# H05-dl.net
KiCad netlist of a schematic drawn in EAGLE
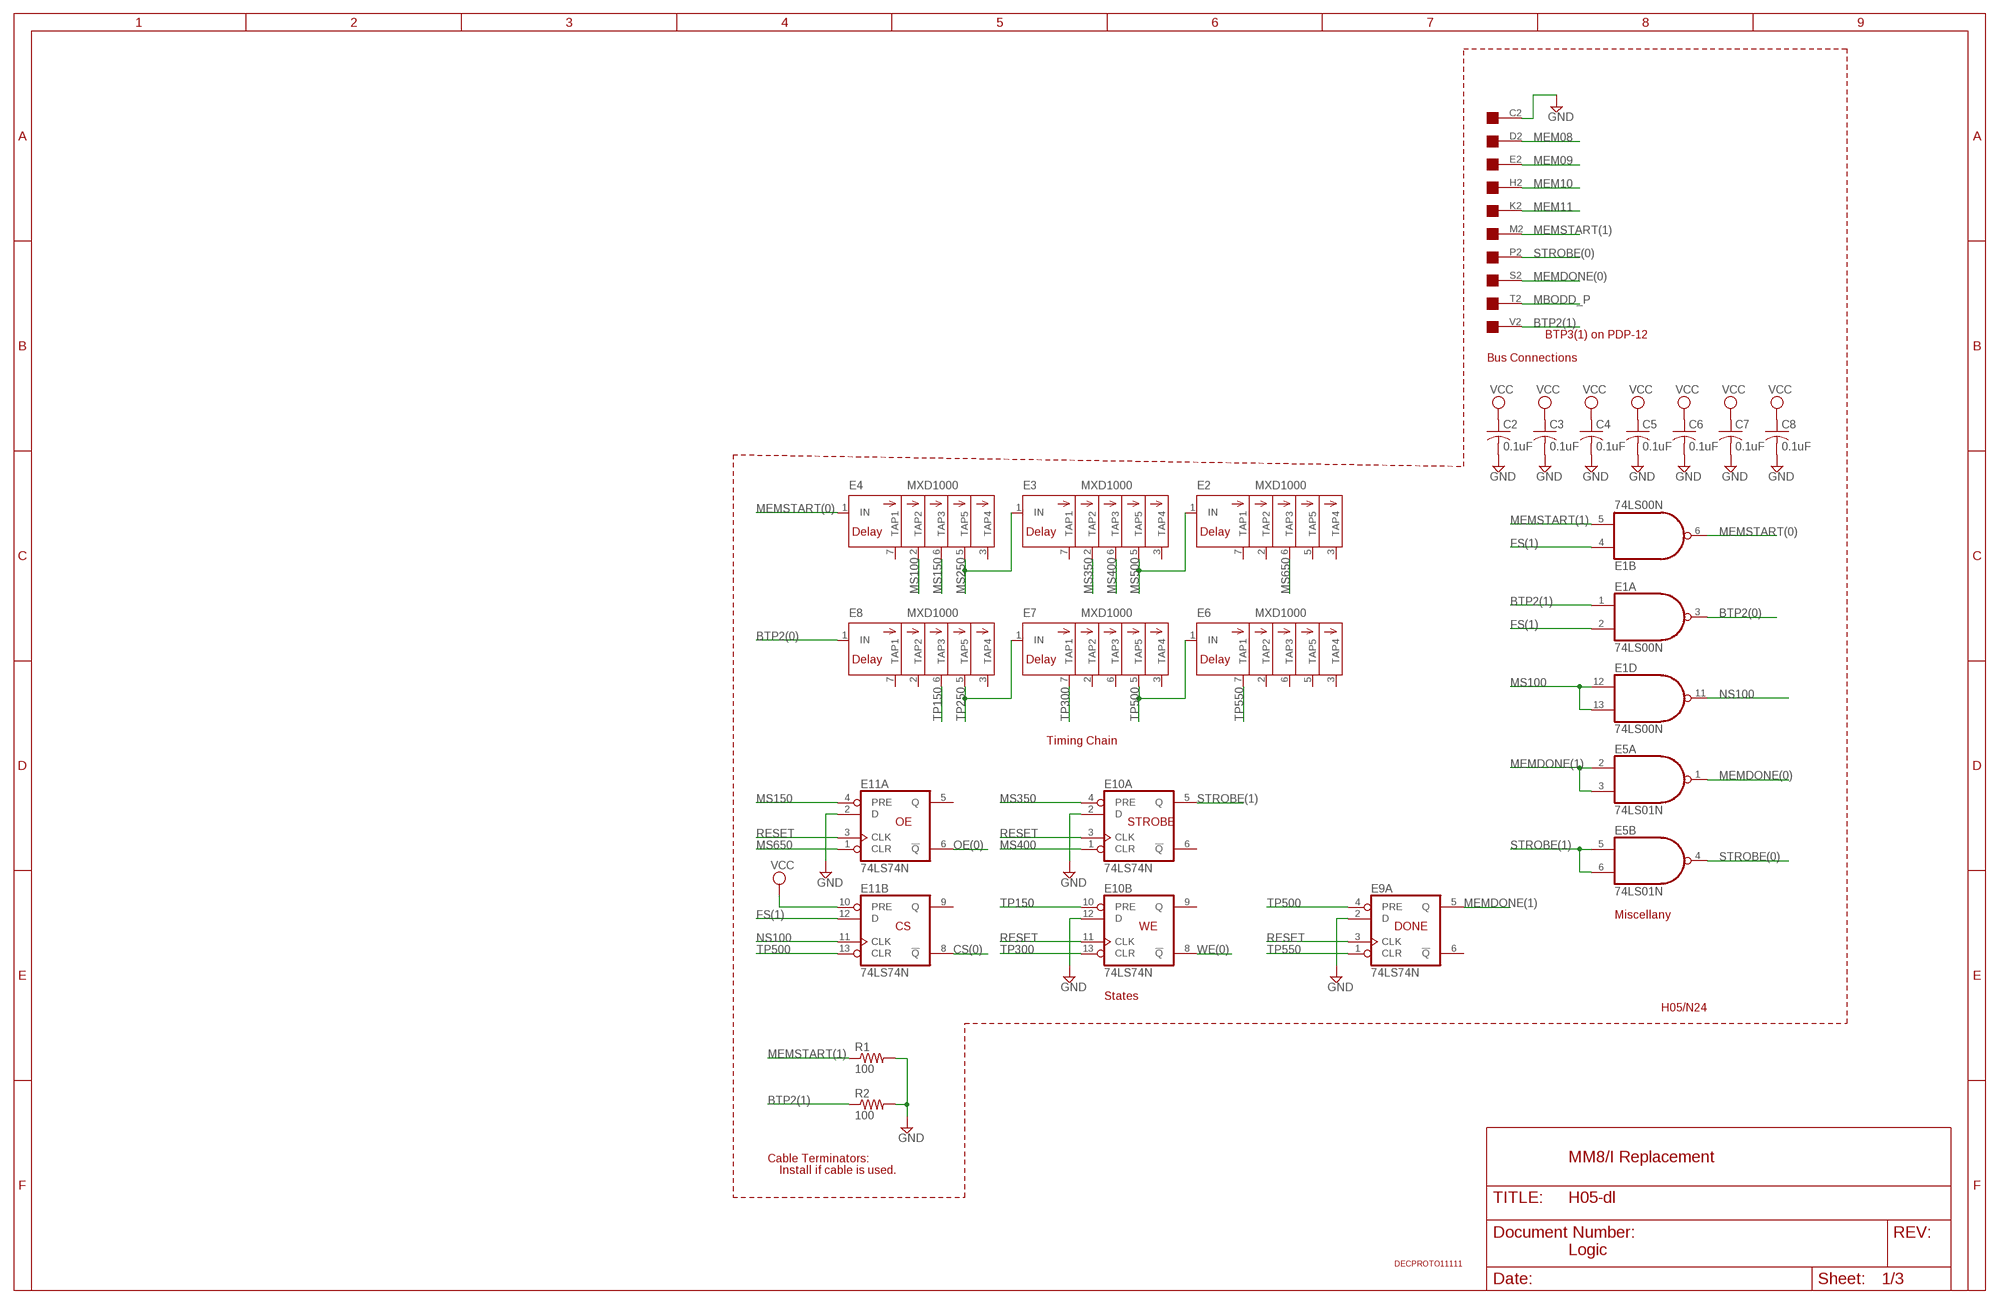
[diagram p0: schematic, sheet 1]
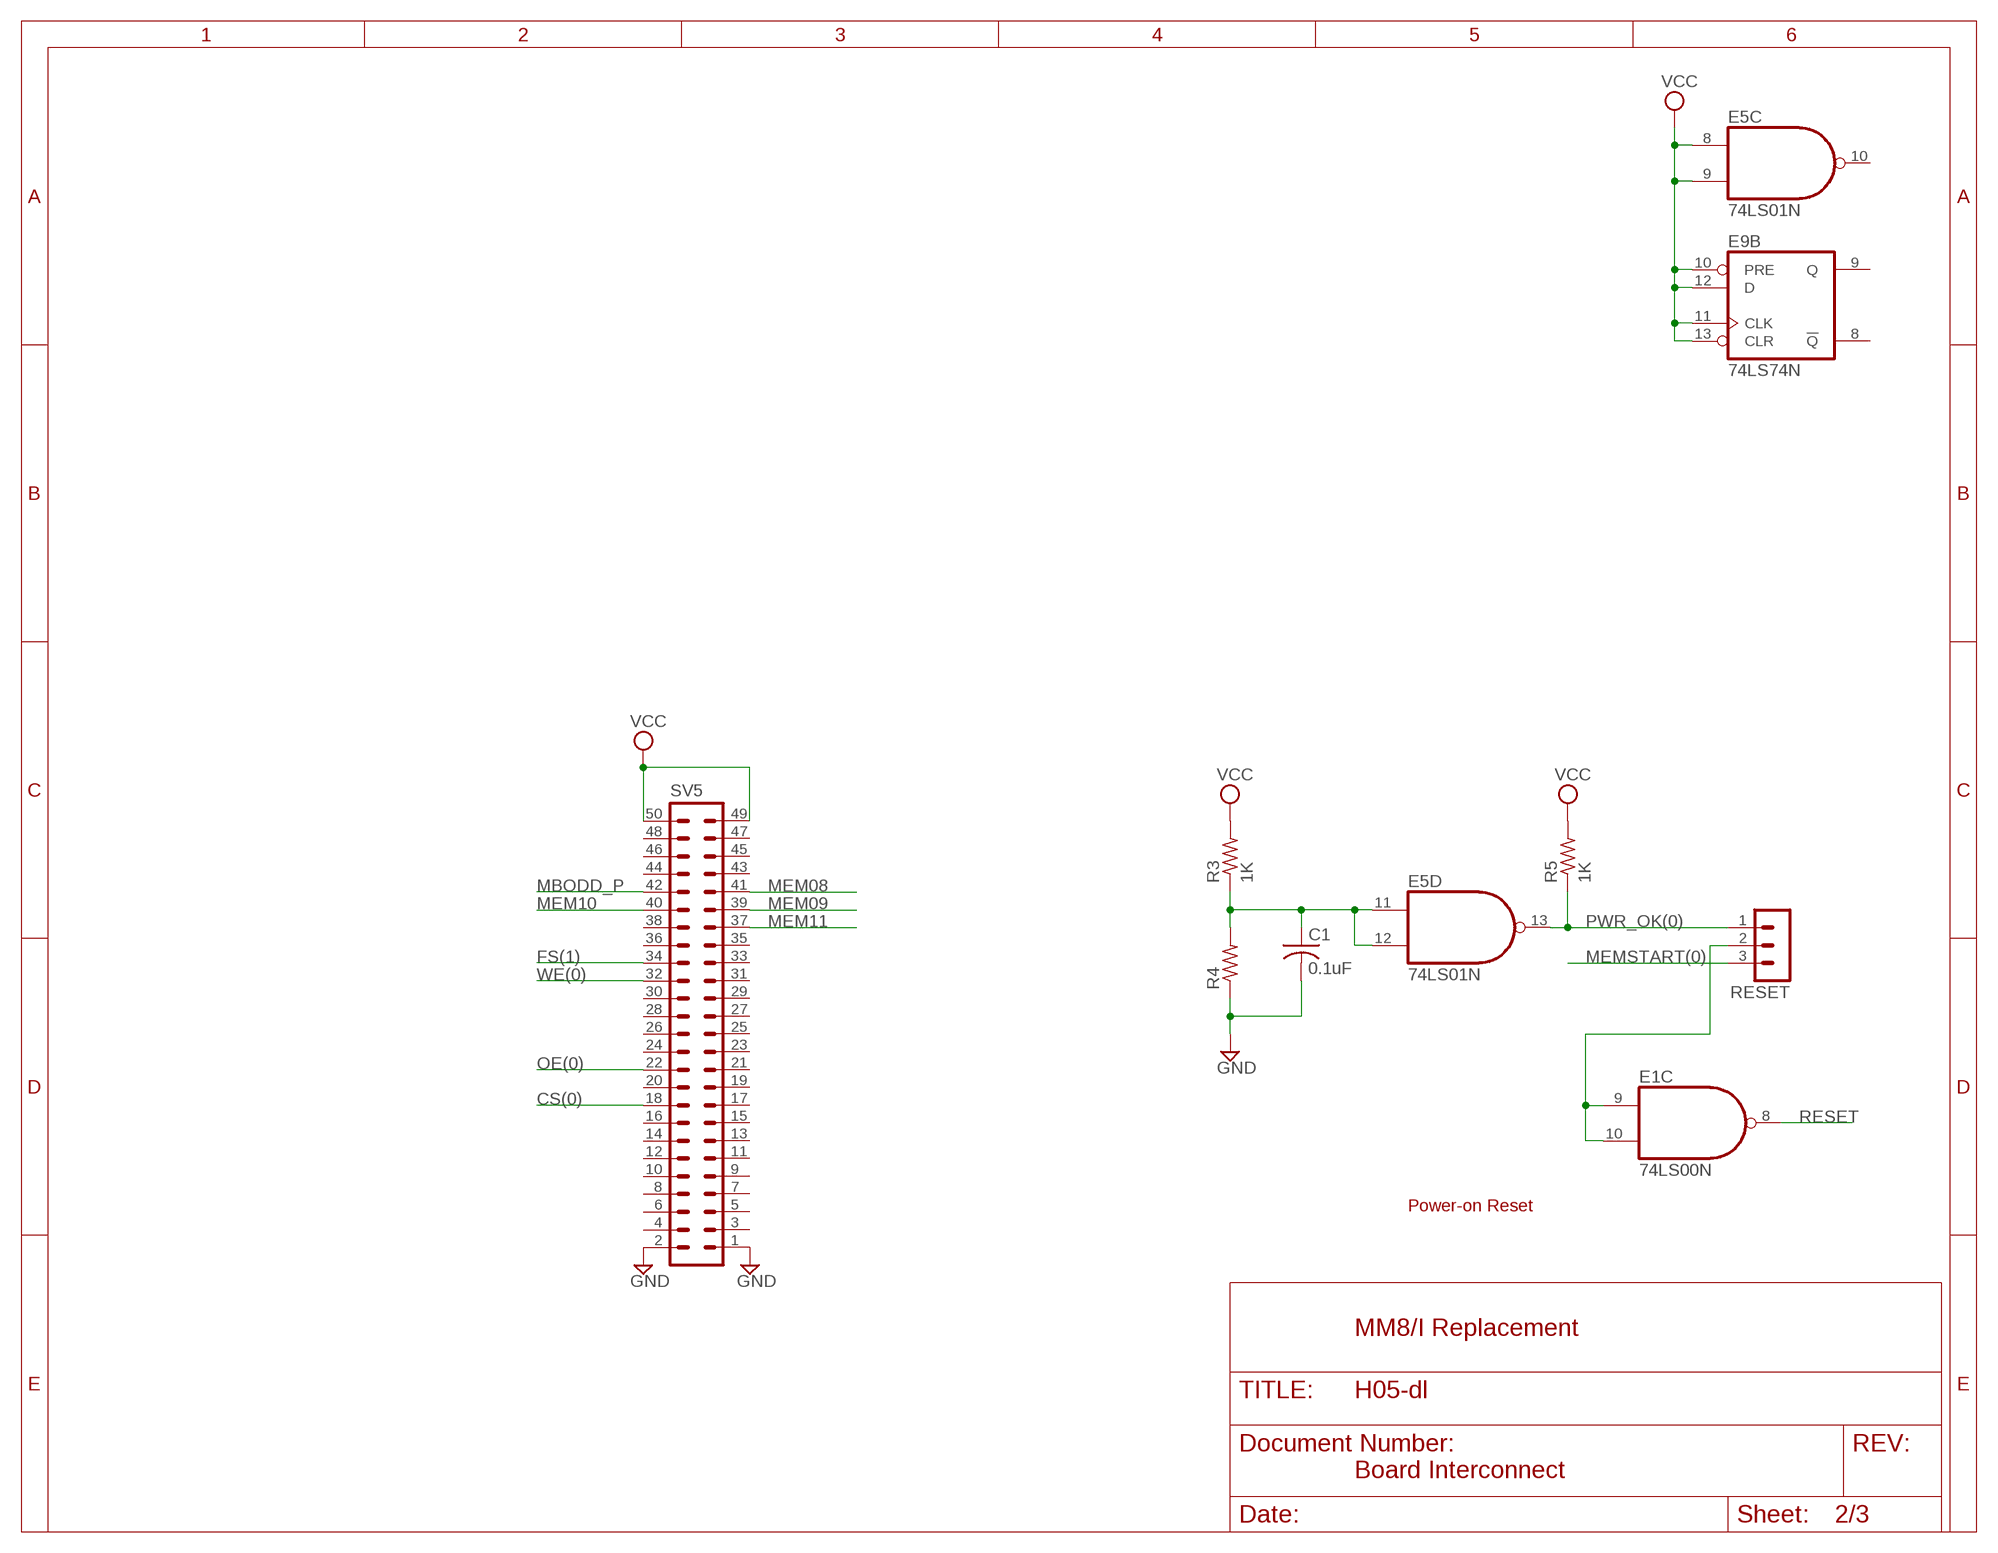
[diagram p1: schematic, sheet 2]
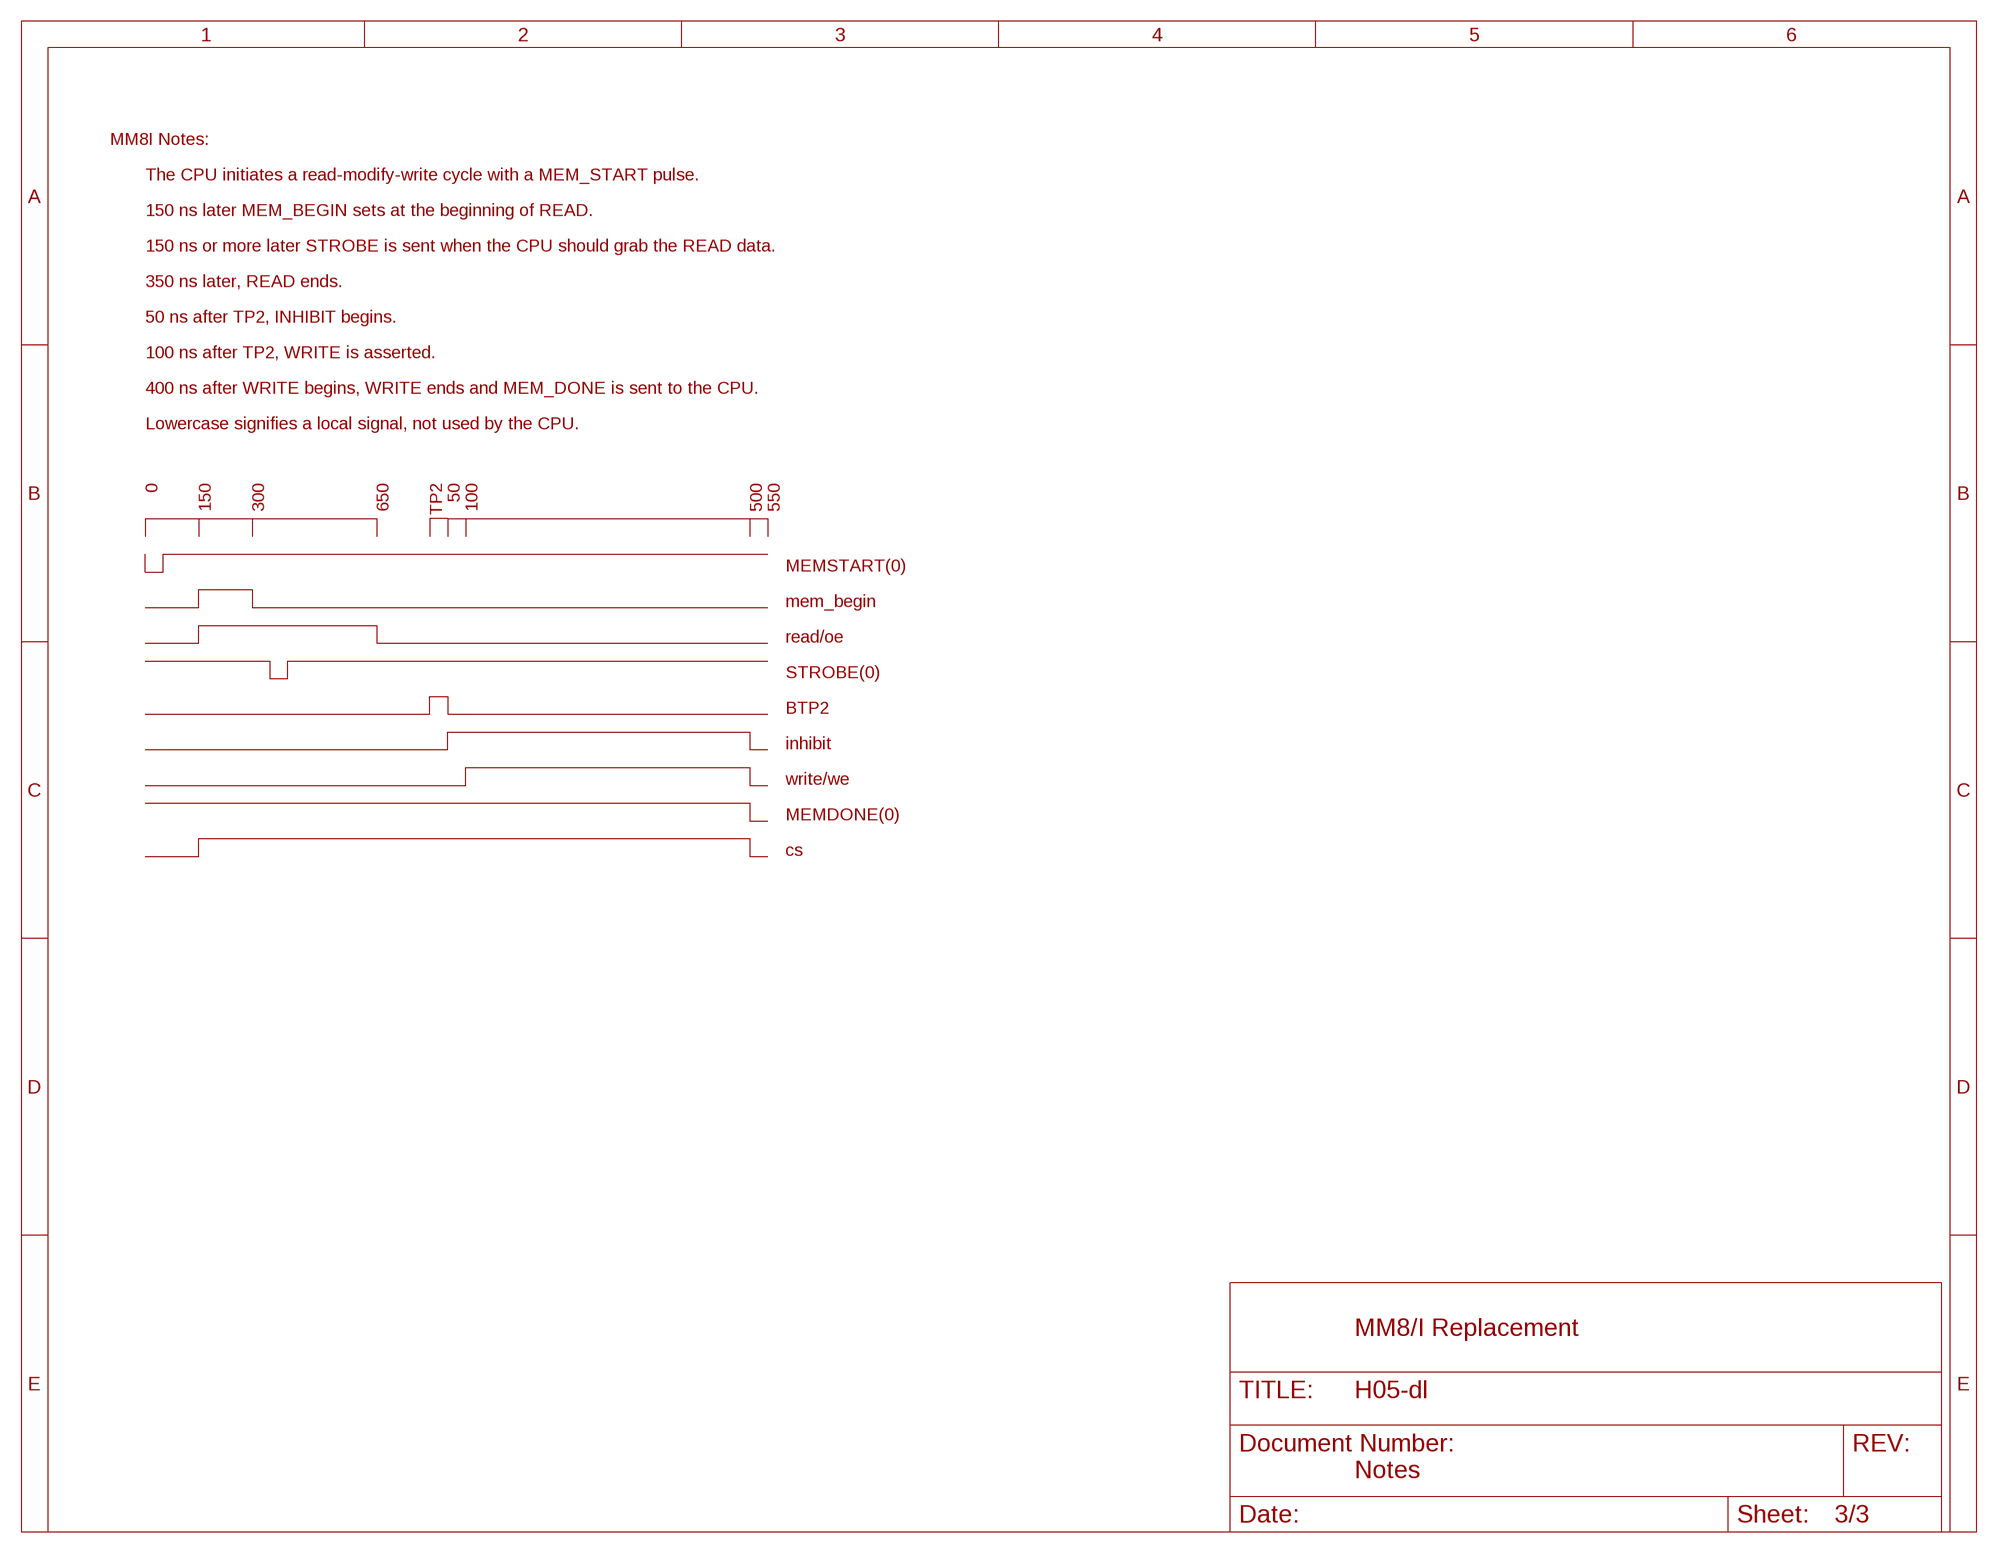
[diagram p2: schematic, sheet 3]

(export (version "E")
  (design (tool "Eeschema 10.0.6"))
  (components
    (comp (ref "C1")
      (value "0.1uF")
      (footprint "eagle-import:C050-025X075")
      (libsource (lib "eagle-import") (part "C-US050-025X075"))
    )
    (comp (ref "E1")
      (value "74LS00N")
      (footprint "eagle-import:DIL14")
      (libsource (lib "eagle-import") (part "7400NLS"))
    )
    (comp (ref "E5")
      (value "74LS01N")
      (footprint "eagle-import:DIL14")
      (libsource (lib "eagle-import") (part "7401NLS"))
    )
    (comp (ref "E9")
      (value "74LS74N")
      (footprint "eagle-import:DIL14")
      (libsource (lib "eagle-import") (part "7474NLS"))
    )
    (comp (ref "R3")
      (value "1K")
      (footprint "eagle-import:0207_10")
      (libsource (lib "eagle-import") (part "R-US_0207/10"))
    )
    (comp (ref "R4")
      (value "R-US_0207/10")
      (footprint "eagle-import:0207_10")
      (libsource (lib "eagle-import") (part "R-US_0207/10"))
    )
    (comp (ref "R5")
      (value "1K")
      (footprint "eagle-import:0207_10")
      (libsource (lib "eagle-import") (part "R-US_0207/10"))
    )
    (comp (ref "RESET")
      (value "MA03-1")
      (footprint "eagle-import:MA03-1")
      (libsource (lib "eagle-import") (part "MA03-1"))
    )
    (comp (ref "SV5")
      (value "ML50L")
      (footprint "eagle-import:ML50L")
      (libsource (lib "eagle-import") (part "ML50L"))
    )
    (comp (ref "C2")
      (value "0.1uF")
      (footprint "eagle-import:C050-025X075")
      (libsource (lib "eagle-import") (part "C-US050-025X075"))
    )
    (comp (ref "C3")
      (value "0.1uF")
      (footprint "eagle-import:C050-025X075")
      (libsource (lib "eagle-import") (part "C-US050-025X075"))
    )
    (comp (ref "C4")
      (value "0.1uF")
      (footprint "eagle-import:C050-025X075")
      (libsource (lib "eagle-import") (part "C-US050-025X075"))
    )
    (comp (ref "C5")
      (value "0.1uF")
      (footprint "eagle-import:C050-025X075")
      (libsource (lib "eagle-import") (part "C-US050-025X075"))
    )
    (comp (ref "C6")
      (value "0.1uF")
      (footprint "eagle-import:C050-025X075")
      (libsource (lib "eagle-import") (part "C-US050-025X075"))
    )
    (comp (ref "C7")
      (value "0.1uF")
      (footprint "eagle-import:C050-025X075")
      (libsource (lib "eagle-import") (part "C-US050-025X075"))
    )
    (comp (ref "C8")
      (value "0.1uF")
      (footprint "eagle-import:C050-025X075")
      (libsource (lib "eagle-import") (part "C-US050-025X075"))
    )
    (comp (ref "E2")
      (value "MXD1000")
      (footprint "eagle-import:DIL08")
      (libsource (lib "eagle-import") (part "MXD1000"))
    )
    (comp (ref "E3")
      (value "MXD1000")
      (footprint "eagle-import:DIL08")
      (libsource (lib "eagle-import") (part "MXD1000"))
    )
    (comp (ref "E4")
      (value "MXD1000")
      (footprint "eagle-import:DIL08")
      (libsource (lib "eagle-import") (part "MXD1000"))
    )
    (comp (ref "E6")
      (value "MXD1000")
      (footprint "eagle-import:DIL08")
      (libsource (lib "eagle-import") (part "MXD1000"))
    )
    (comp (ref "E7")
      (value "MXD1000")
      (footprint "eagle-import:DIL08")
      (libsource (lib "eagle-import") (part "MXD1000"))
    )
    (comp (ref "E8")
      (value "MXD1000")
      (footprint "eagle-import:DIL08")
      (libsource (lib "eagle-import") (part "MXD1000"))
    )
    (comp (ref "E10")
      (value "74LS74N")
      (footprint "eagle-import:DIL14")
      (libsource (lib "eagle-import") (part "7474NLS"))
    )
    (comp (ref "E11")
      (value "74LS74N")
      (footprint "eagle-import:DIL14")
      (libsource (lib "eagle-import") (part "7474NLS"))
    )
    (comp (ref "H05")
      (value "EDGE-1")
      (footprint "eagle-import:EDGE-CON1")
      (libsource (lib "eagle-import") (part "EDGE-1"))
    )
    (comp (ref "R1")
      (value "100")
      (footprint "eagle-import:0207_10")
      (libsource (lib "eagle-import") (part "R-US_0207/10"))
    )
    (comp (ref "R2")
      (value "100")
      (footprint "eagle-import:0207_10")
      (libsource (lib "eagle-import") (part "R-US_0207/10"))
    )
    (comp (ref "U$6")
      (value "DECPROTO11111")
      (footprint "eagle-import:DECPROTO11111")
      (libsource (lib "eagle-import") (part "DECPROTO11111"))
    )
  )
  (nets
    (net (code "1") (name "BTP2(0)") (class "Default")
      (node (ref "E1") (pin "3") (pinfunction "O_3") (pintype "output"))
      (node (ref "E8") (pin "1") (pinfunction "IN_1") (pintype "input"))
    )
    (net (code "2") (name "BTP2(1)") (class "Default")
      (node (ref "E1") (pin "1") (pinfunction "I0_1") (pintype "input"))
      (node (ref "H05") (pin "V2") (pinfunction "1_V2") (pintype "bidirectional"))
      (node (ref "R2") (pin "1") (pinfunction "1_1") (pintype "passive"))
    )
    (net (code "3") (name "CS(0)") (class "Default")
      (node (ref "E11") (pin "8") (pinfunction "~{Q}_8") (pintype "output"))
      (node (ref "SV5") (pin "18") (pinfunction "18_18") (pintype "passive"))
    )
    (net (code "4") (name "FS(1)") (class "Default")
      (node (ref "E1") (pin "2") (pinfunction "I1_2") (pintype "input"))
      (node (ref "E1") (pin "4") (pinfunction "I0_4") (pintype "input"))
      (node (ref "E11") (pin "12") (pinfunction "D_12") (pintype "input"))
      (node (ref "SV5") (pin "34") (pinfunction "34_34") (pintype "passive"))
    )
    (net (code "5") (name "GND") (class "Default")
      (node (ref "C1") (pin "2") (pinfunction "2_2") (pintype "passive"))
      (node (ref "C2") (pin "2") (pinfunction "2_2") (pintype "passive"))
      (node (ref "C3") (pin "2") (pinfunction "2_2") (pintype "passive"))
      (node (ref "C4") (pin "2") (pinfunction "2_2") (pintype "passive"))
      (node (ref "C5") (pin "2") (pinfunction "2_2") (pintype "passive"))
      (node (ref "C6") (pin "2") (pinfunction "2_2") (pintype "passive"))
      (node (ref "C7") (pin "2") (pinfunction "2_2") (pintype "passive"))
      (node (ref "C8") (pin "2") (pinfunction "2_2") (pintype "passive"))
      (node (ref "E10") (pin "12") (pinfunction "D_12") (pintype "input"))
      (node (ref "E10") (pin "2") (pinfunction "D_2") (pintype "input"))
      (node (ref "E11") (pin "2") (pinfunction "D_2") (pintype "input"))
      (node (ref "E9") (pin "2") (pinfunction "D_2") (pintype "input"))
      (node (ref "H05") (pin "C2") (pinfunction "1_C2") (pintype "bidirectional"))
      (node (ref "R1") (pin "2") (pinfunction "2_2") (pintype "passive"))
      (node (ref "R2") (pin "2") (pinfunction "2_2") (pintype "passive"))
      (node (ref "R4") (pin "1") (pinfunction "1_1") (pintype "passive"))
      (node (ref "SV5") (pin "1") (pinfunction "1_1") (pintype "passive"))
      (node (ref "SV5") (pin "2") (pinfunction "2_2") (pintype "passive"))
    )
    (net (code "6") (name "MBODD_P") (class "Default")
      (node (ref "H05") (pin "T2") (pinfunction "1_T2") (pintype "bidirectional"))
      (node (ref "SV5") (pin "42") (pinfunction "42_42") (pintype "passive"))
    )
    (net (code "7") (name "MEM08") (class "Default")
      (node (ref "H05") (pin "D2") (pinfunction "1_D2") (pintype "bidirectional"))
      (node (ref "SV5") (pin "41") (pinfunction "41_41") (pintype "passive"))
    )
    (net (code "8") (name "MEM09") (class "Default")
      (node (ref "H05") (pin "E2") (pinfunction "1_E2") (pintype "bidirectional"))
      (node (ref "SV5") (pin "39") (pinfunction "39_39") (pintype "passive"))
    )
    (net (code "9") (name "MEM10") (class "Default")
      (node (ref "H05") (pin "H2") (pinfunction "1_H2") (pintype "bidirectional"))
      (node (ref "SV5") (pin "40") (pinfunction "40_40") (pintype "passive"))
    )
    (net (code "10") (name "MEM11") (class "Default")
      (node (ref "H05") (pin "K2") (pinfunction "1_K2") (pintype "bidirectional"))
      (node (ref "SV5") (pin "37") (pinfunction "37_37") (pintype "passive"))
    )
    (net (code "11") (name "MEMDONE(0)") (class "Default")
      (node (ref "E5") (pin "1") (pinfunction "O_1") (pintype "open_collector"))
      (node (ref "H05") (pin "S2") (pinfunction "1_S2") (pintype "bidirectional"))
    )
    (net (code "12") (name "MEMDONE(1)") (class "Default")
      (node (ref "E5") (pin "2") (pinfunction "I0_2") (pintype "input"))
      (node (ref "E5") (pin "3") (pinfunction "I1_3") (pintype "input"))
      (node (ref "E9") (pin "5") (pinfunction "Q_5") (pintype "output"))
    )
    (net (code "13") (name "MEMSTART(0)") (class "Default")
      (node (ref "E1") (pin "6") (pinfunction "O_6") (pintype "output"))
      (node (ref "E4") (pin "1") (pinfunction "IN_1") (pintype "input"))
      (node (ref "RESET") (pin "3") (pinfunction "3_3") (pintype "passive"))
    )
    (net (code "14") (name "MEMSTART(1)") (class "Default")
      (node (ref "E1") (pin "5") (pinfunction "I1_5") (pintype "input"))
      (node (ref "H05") (pin "M2") (pinfunction "1_M2") (pintype "bidirectional"))
      (node (ref "R1") (pin "1") (pinfunction "1_1") (pintype "passive"))
    )
    (net (code "15") (name "MS100") (class "Default")
      (node (ref "E1") (pin "12") (pinfunction "I0_12") (pintype "input"))
      (node (ref "E1") (pin "13") (pinfunction "I1_13") (pintype "input"))
      (node (ref "E4") (pin "2") (pinfunction "TAP2_2") (pintype "output"))
    )
    (net (code "16") (name "MS150") (class "Default")
      (node (ref "E11") (pin "4") (pinfunction "PRE_4") (pintype "input"))
      (node (ref "E4") (pin "6") (pinfunction "TAP3_6") (pintype "output"))
    )
    (net (code "17") (name "MS250") (class "Default")
      (node (ref "E3") (pin "1") (pinfunction "IN_1") (pintype "input"))
      (node (ref "E4") (pin "5") (pinfunction "TAP5_5") (pintype "output"))
    )
    (net (code "18") (name "MS350") (class "Default")
      (node (ref "E10") (pin "4") (pinfunction "PRE_4") (pintype "input"))
      (node (ref "E3") (pin "2") (pinfunction "TAP2_2") (pintype "output"))
    )
    (net (code "19") (name "MS400") (class "Default")
      (node (ref "E10") (pin "1") (pinfunction "CLR_1") (pintype "input"))
      (node (ref "E3") (pin "6") (pinfunction "TAP3_6") (pintype "output"))
    )
    (net (code "20") (name "MS500") (class "Default")
      (node (ref "E2") (pin "1") (pinfunction "IN_1") (pintype "input"))
      (node (ref "E3") (pin "5") (pinfunction "TAP5_5") (pintype "output"))
    )
    (net (code "21") (name "MS650") (class "Default")
      (node (ref "E11") (pin "1") (pinfunction "CLR_1") (pintype "input"))
      (node (ref "E2") (pin "6") (pinfunction "TAP3_6") (pintype "output"))
    )
    (net (code "22") (name "NS100") (class "Default")
      (node (ref "E1") (pin "11") (pinfunction "O_11") (pintype "output"))
      (node (ref "E11") (pin "11") (pinfunction "CLK_11") (pintype "input"))
    )
    (net (code "23") (name "Net-(E1C-I0)") (class "Default")
      (node (ref "E1") (pin "10") (pinfunction "I1_10") (pintype "input"))
      (node (ref "E1") (pin "9") (pinfunction "I0_9") (pintype "input"))
      (node (ref "RESET") (pin "2") (pinfunction "2_2") (pintype "passive"))
    )
    (net (code "24") (name "Net-(E5D-I0)") (class "Default")
      (node (ref "C1") (pin "1") (pinfunction "1_1") (pintype "passive"))
      (node (ref "E5") (pin "11") (pinfunction "I0_11") (pintype "input"))
      (node (ref "E5") (pin "12") (pinfunction "I1_12") (pintype "input"))
      (node (ref "R3") (pin "1") (pinfunction "1_1") (pintype "passive"))
      (node (ref "R4") (pin "2") (pinfunction "2_2") (pintype "passive"))
    )
    (net (code "25") (name "OE(0)") (class "Default")
      (node (ref "E11") (pin "6") (pinfunction "~{Q}_6") (pintype "output"))
      (node (ref "SV5") (pin "22") (pinfunction "22_22") (pintype "passive"))
    )
    (net (code "26") (name "PWR_OK(0)") (class "Default")
      (node (ref "E5") (pin "13") (pinfunction "O_13") (pintype "open_collector"))
      (node (ref "R5") (pin "1") (pinfunction "1_1") (pintype "passive"))
      (node (ref "RESET") (pin "1") (pinfunction "1_1") (pintype "passive"))
    )
    (net (code "27") (name "RESET") (class "Default")
      (node (ref "E1") (pin "8") (pinfunction "O_8") (pintype "output"))
      (node (ref "E10") (pin "11") (pinfunction "CLK_11") (pintype "input"))
      (node (ref "E10") (pin "3") (pinfunction "CLK_3") (pintype "input"))
      (node (ref "E11") (pin "3") (pinfunction "CLK_3") (pintype "input"))
      (node (ref "E9") (pin "3") (pinfunction "CLK_3") (pintype "input"))
    )
    (net (code "28") (name "STROBE(0)") (class "Default")
      (node (ref "E5") (pin "4") (pinfunction "O_4") (pintype "open_collector"))
      (node (ref "H05") (pin "P2") (pinfunction "1_P2") (pintype "bidirectional"))
    )
    (net (code "29") (name "STROBE(1)") (class "Default")
      (node (ref "E10") (pin "5") (pinfunction "Q_5") (pintype "output"))
      (node (ref "E5") (pin "5") (pinfunction "I0_5") (pintype "input"))
      (node (ref "E5") (pin "6") (pinfunction "I1_6") (pintype "input"))
    )
    (net (code "30") (name "TP150") (class "Default")
      (node (ref "E10") (pin "10") (pinfunction "PRE_10") (pintype "input"))
      (node (ref "E8") (pin "6") (pinfunction "TAP3_6") (pintype "output"))
    )
    (net (code "31") (name "TP250") (class "Default")
      (node (ref "E7") (pin "1") (pinfunction "IN_1") (pintype "input"))
      (node (ref "E8") (pin "5") (pinfunction "TAP5_5") (pintype "output"))
    )
    (net (code "32") (name "TP300") (class "Default")
      (node (ref "E10") (pin "13") (pinfunction "CLR_13") (pintype "input"))
      (node (ref "E7") (pin "7") (pinfunction "TAP1_7") (pintype "output"))
    )
    (net (code "33") (name "TP500") (class "Default")
      (node (ref "E11") (pin "13") (pinfunction "CLR_13") (pintype "input"))
      (node (ref "E6") (pin "1") (pinfunction "IN_1") (pintype "input"))
      (node (ref "E7") (pin "5") (pinfunction "TAP5_5") (pintype "output"))
      (node (ref "E9") (pin "4") (pinfunction "PRE_4") (pintype "input"))
    )
    (net (code "34") (name "TP550") (class "Default")
      (node (ref "E6") (pin "7") (pinfunction "TAP1_7") (pintype "output"))
      (node (ref "E9") (pin "1") (pinfunction "CLR_1") (pintype "input"))
    )
    (net (code "35") (name "VCC") (class "Default")
      (node (ref "C2") (pin "1") (pinfunction "1_1") (pintype "passive"))
      (node (ref "C3") (pin "1") (pinfunction "1_1") (pintype "passive"))
      (node (ref "C4") (pin "1") (pinfunction "1_1") (pintype "passive"))
      (node (ref "C5") (pin "1") (pinfunction "1_1") (pintype "passive"))
      (node (ref "C6") (pin "1") (pinfunction "1_1") (pintype "passive"))
      (node (ref "C7") (pin "1") (pinfunction "1_1") (pintype "passive"))
      (node (ref "C8") (pin "1") (pinfunction "1_1") (pintype "passive"))
      (node (ref "E11") (pin "10") (pinfunction "PRE_10") (pintype "input"))
      (node (ref "E5") (pin "8") (pinfunction "I0_8") (pintype "input"))
      (node (ref "E5") (pin "9") (pinfunction "I1_9") (pintype "input"))
      (node (ref "E9") (pin "10") (pinfunction "PRE_10") (pintype "input"))
      (node (ref "E9") (pin "11") (pinfunction "CLK_11") (pintype "input"))
      (node (ref "E9") (pin "12") (pinfunction "D_12") (pintype "input"))
      (node (ref "E9") (pin "13") (pinfunction "CLR_13") (pintype "input"))
      (node (ref "R3") (pin "2") (pinfunction "2_2") (pintype "passive"))
      (node (ref "R5") (pin "2") (pinfunction "2_2") (pintype "passive"))
      (node (ref "SV5") (pin "49") (pinfunction "49_49") (pintype "passive"))
      (node (ref "SV5") (pin "50") (pinfunction "50_50") (pintype "passive"))
    )
    (net (code "36") (name "WE(0)") (class "Default")
      (node (ref "E10") (pin "8") (pinfunction "~{Q}_8") (pintype "output"))
      (node (ref "SV5") (pin "32") (pinfunction "32_32") (pintype "passive"))
    )
    (net (code "37") (name "unconnected-(E2A-TAP1-Pad7)") (class "Default")
      (node (ref "E2") (pin "7") (pinfunction "TAP1_7") (pintype "output"))
    )
    (net (code "38") (name "unconnected-(E2A-TAP2-Pad2)") (class "Default")
      (node (ref "E2") (pin "2") (pinfunction "TAP2_2") (pintype "output"))
    )
    (net (code "39") (name "unconnected-(E2A-TAP4-Pad3)") (class "Default")
      (node (ref "E2") (pin "3") (pinfunction "TAP4_3") (pintype "output"))
    )
    (net (code "40") (name "unconnected-(E2A-TAP5-Pad5)") (class "Default")
      (node (ref "E2") (pin "5") (pinfunction "TAP5_5") (pintype "output"))
    )
    (net (code "41") (name "unconnected-(E3A-TAP1-Pad7)") (class "Default")
      (node (ref "E3") (pin "7") (pinfunction "TAP1_7") (pintype "output"))
    )
    (net (code "42") (name "unconnected-(E3A-TAP4-Pad3)") (class "Default")
      (node (ref "E3") (pin "3") (pinfunction "TAP4_3") (pintype "output"))
    )
    (net (code "43") (name "unconnected-(E4A-TAP1-Pad7)") (class "Default")
      (node (ref "E4") (pin "7") (pinfunction "TAP1_7") (pintype "output"))
    )
    (net (code "44") (name "unconnected-(E4A-TAP4-Pad3)") (class "Default")
      (node (ref "E4") (pin "3") (pinfunction "TAP4_3") (pintype "output"))
    )
    (net (code "45") (name "unconnected-(E5C-O-Pad10)") (class "Default")
      (node (ref "E5") (pin "10") (pinfunction "O_10") (pintype "open_collector"))
    )
    (net (code "46") (name "unconnected-(E6A-TAP2-Pad2)") (class "Default")
      (node (ref "E6") (pin "2") (pinfunction "TAP2_2") (pintype "output"))
    )
    (net (code "47") (name "unconnected-(E6A-TAP3-Pad6)") (class "Default")
      (node (ref "E6") (pin "6") (pinfunction "TAP3_6") (pintype "output"))
    )
    (net (code "48") (name "unconnected-(E6A-TAP4-Pad3)") (class "Default")
      (node (ref "E6") (pin "3") (pinfunction "TAP4_3") (pintype "output"))
    )
    (net (code "49") (name "unconnected-(E6A-TAP5-Pad5)") (class "Default")
      (node (ref "E6") (pin "5") (pinfunction "TAP5_5") (pintype "output"))
    )
    (net (code "50") (name "unconnected-(E7A-TAP2-Pad2)") (class "Default")
      (node (ref "E7") (pin "2") (pinfunction "TAP2_2") (pintype "output"))
    )
    (net (code "51") (name "unconnected-(E7A-TAP3-Pad6)") (class "Default")
      (node (ref "E7") (pin "6") (pinfunction "TAP3_6") (pintype "output"))
    )
    (net (code "52") (name "unconnected-(E7A-TAP4-Pad3)") (class "Default")
      (node (ref "E7") (pin "3") (pinfunction "TAP4_3") (pintype "output"))
    )
    (net (code "53") (name "unconnected-(E8A-TAP1-Pad7)") (class "Default")
      (node (ref "E8") (pin "7") (pinfunction "TAP1_7") (pintype "output"))
    )
    (net (code "54") (name "unconnected-(E8A-TAP2-Pad2)") (class "Default")
      (node (ref "E8") (pin "2") (pinfunction "TAP2_2") (pintype "output"))
    )
    (net (code "55") (name "unconnected-(E8A-TAP4-Pad3)") (class "Default")
      (node (ref "E8") (pin "3") (pinfunction "TAP4_3") (pintype "output"))
    )
    (net (code "56") (name "unconnected-(E9A-~{Q}-Pad6)") (class "Default")
      (node (ref "E9") (pin "6") (pinfunction "~{Q}_6") (pintype "output"))
    )
    (net (code "57") (name "unconnected-(E9B-Q-Pad9)") (class "Default")
      (node (ref "E9") (pin "9") (pinfunction "Q_9") (pintype "output"))
    )
    (net (code "58") (name "unconnected-(E9B-~{Q}-Pad8)") (class "Default")
      (node (ref "E9") (pin "8") (pinfunction "~{Q}_8") (pintype "output"))
    )
    (net (code "59") (name "unconnected-(E10A-~{Q}-Pad6)") (class "Default")
      (node (ref "E10") (pin "6") (pinfunction "~{Q}_6") (pintype "output"))
    )
    (net (code "60") (name "unconnected-(E10B-Q-Pad9)") (class "Default")
      (node (ref "E10") (pin "9") (pinfunction "Q_9") (pintype "output"))
    )
    (net (code "61") (name "unconnected-(E11A-Q-Pad5)") (class "Default")
      (node (ref "E11") (pin "5") (pinfunction "Q_5") (pintype "output"))
    )
    (net (code "62") (name "unconnected-(E11B-Q-Pad9)") (class "Default")
      (node (ref "E11") (pin "9") (pinfunction "Q_9") (pintype "output"))
    )
    (net (code "63") (name "unconnected-(SV5-Pad3)") (class "Default")
      (node (ref "SV5") (pin "3") (pinfunction "3_3") (pintype "passive"))
    )
    (net (code "64") (name "unconnected-(SV5-Pad4)") (class "Default")
      (node (ref "SV5") (pin "4") (pinfunction "4_4") (pintype "passive"))
    )
    (net (code "65") (name "unconnected-(SV5-Pad5)") (class "Default")
      (node (ref "SV5") (pin "5") (pinfunction "5_5") (pintype "passive"))
    )
    (net (code "66") (name "unconnected-(SV5-Pad6)") (class "Default")
      (node (ref "SV5") (pin "6") (pinfunction "6_6") (pintype "passive"))
    )
    (net (code "67") (name "unconnected-(SV5-Pad7)") (class "Default")
      (node (ref "SV5") (pin "7") (pinfunction "7_7") (pintype "passive"))
    )
    (net (code "68") (name "unconnected-(SV5-Pad8)") (class "Default")
      (node (ref "SV5") (pin "8") (pinfunction "8_8") (pintype "passive"))
    )
    (net (code "69") (name "unconnected-(SV5-Pad9)") (class "Default")
      (node (ref "SV5") (pin "9") (pinfunction "9_9") (pintype "passive"))
    )
    (net (code "70") (name "unconnected-(SV5-Pad10)") (class "Default")
      (node (ref "SV5") (pin "10") (pinfunction "10_10") (pintype "passive"))
    )
    (net (code "71") (name "unconnected-(SV5-Pad11)") (class "Default")
      (node (ref "SV5") (pin "11") (pinfunction "11_11") (pintype "passive"))
    )
    (net (code "72") (name "unconnected-(SV5-Pad12)") (class "Default")
      (node (ref "SV5") (pin "12") (pinfunction "12_12") (pintype "passive"))
    )
    (net (code "73") (name "unconnected-(SV5-Pad13)") (class "Default")
      (node (ref "SV5") (pin "13") (pinfunction "13_13") (pintype "passive"))
    )
    (net (code "74") (name "unconnected-(SV5-Pad14)") (class "Default")
      (node (ref "SV5") (pin "14") (pinfunction "14_14") (pintype "passive"))
    )
    (net (code "75") (name "unconnected-(SV5-Pad15)") (class "Default")
      (node (ref "SV5") (pin "15") (pinfunction "15_15") (pintype "passive"))
    )
    (net (code "76") (name "unconnected-(SV5-Pad16)") (class "Default")
      (node (ref "SV5") (pin "16") (pinfunction "16_16") (pintype "passive"))
    )
    (net (code "77") (name "unconnected-(SV5-Pad17)") (class "Default")
      (node (ref "SV5") (pin "17") (pinfunction "17_17") (pintype "passive"))
    )
    (net (code "78") (name "unconnected-(SV5-Pad19)") (class "Default")
      (node (ref "SV5") (pin "19") (pinfunction "19_19") (pintype "passive"))
    )
    (net (code "79") (name "unconnected-(SV5-Pad20)") (class "Default")
      (node (ref "SV5") (pin "20") (pinfunction "20_20") (pintype "passive"))
    )
    (net (code "80") (name "unconnected-(SV5-Pad21)") (class "Default")
      (node (ref "SV5") (pin "21") (pinfunction "21_21") (pintype "passive"))
    )
    (net (code "81") (name "unconnected-(SV5-Pad23)") (class "Default")
      (node (ref "SV5") (pin "23") (pinfunction "23_23") (pintype "passive"))
    )
    (net (code "82") (name "unconnected-(SV5-Pad24)") (class "Default")
      (node (ref "SV5") (pin "24") (pinfunction "24_24") (pintype "passive"))
    )
    (net (code "83") (name "unconnected-(SV5-Pad25)") (class "Default")
      (node (ref "SV5") (pin "25") (pinfunction "25_25") (pintype "passive"))
    )
    (net (code "84") (name "unconnected-(SV5-Pad26)") (class "Default")
      (node (ref "SV5") (pin "26") (pinfunction "26_26") (pintype "passive"))
    )
    (net (code "85") (name "unconnected-(SV5-Pad27)") (class "Default")
      (node (ref "SV5") (pin "27") (pinfunction "27_27") (pintype "passive"))
    )
    (net (code "86") (name "unconnected-(SV5-Pad28)") (class "Default")
      (node (ref "SV5") (pin "28") (pinfunction "28_28") (pintype "passive"))
    )
    (net (code "87") (name "unconnected-(SV5-Pad29)") (class "Default")
      (node (ref "SV5") (pin "29") (pinfunction "29_29") (pintype "passive"))
    )
    (net (code "88") (name "unconnected-(SV5-Pad30)") (class "Default")
      (node (ref "SV5") (pin "30") (pinfunction "30_30") (pintype "passive"))
    )
    (net (code "89") (name "unconnected-(SV5-Pad31)") (class "Default")
      (node (ref "SV5") (pin "31") (pinfunction "31_31") (pintype "passive"))
    )
    (net (code "90") (name "unconnected-(SV5-Pad33)") (class "Default")
      (node (ref "SV5") (pin "33") (pinfunction "33_33") (pintype "passive"))
    )
    (net (code "91") (name "unconnected-(SV5-Pad35)") (class "Default")
      (node (ref "SV5") (pin "35") (pinfunction "35_35") (pintype "passive"))
    )
    (net (code "92") (name "unconnected-(SV5-Pad36)") (class "Default")
      (node (ref "SV5") (pin "36") (pinfunction "36_36") (pintype "passive"))
    )
    (net (code "93") (name "unconnected-(SV5-Pad38)") (class "Default")
      (node (ref "SV5") (pin "38") (pinfunction "38_38") (pintype "passive"))
    )
    (net (code "94") (name "unconnected-(SV5-Pad43)") (class "Default")
      (node (ref "SV5") (pin "43") (pinfunction "43_43") (pintype "passive"))
    )
    (net (code "95") (name "unconnected-(SV5-Pad44)") (class "Default")
      (node (ref "SV5") (pin "44") (pinfunction "44_44") (pintype "passive"))
    )
    (net (code "96") (name "unconnected-(SV5-Pad45)") (class "Default")
      (node (ref "SV5") (pin "45") (pinfunction "45_45") (pintype "passive"))
    )
    (net (code "97") (name "unconnected-(SV5-Pad46)") (class "Default")
      (node (ref "SV5") (pin "46") (pinfunction "46_46") (pintype "passive"))
    )
    (net (code "98") (name "unconnected-(SV5-Pad47)") (class "Default")
      (node (ref "SV5") (pin "47") (pinfunction "47_47") (pintype "passive"))
    )
    (net (code "99") (name "unconnected-(SV5-Pad48)") (class "Default")
      (node (ref "SV5") (pin "48") (pinfunction "48_48") (pintype "passive"))
    )
  )
)
